# PR9002.net
KiCad netlist of a schematic drawn in EAGLE
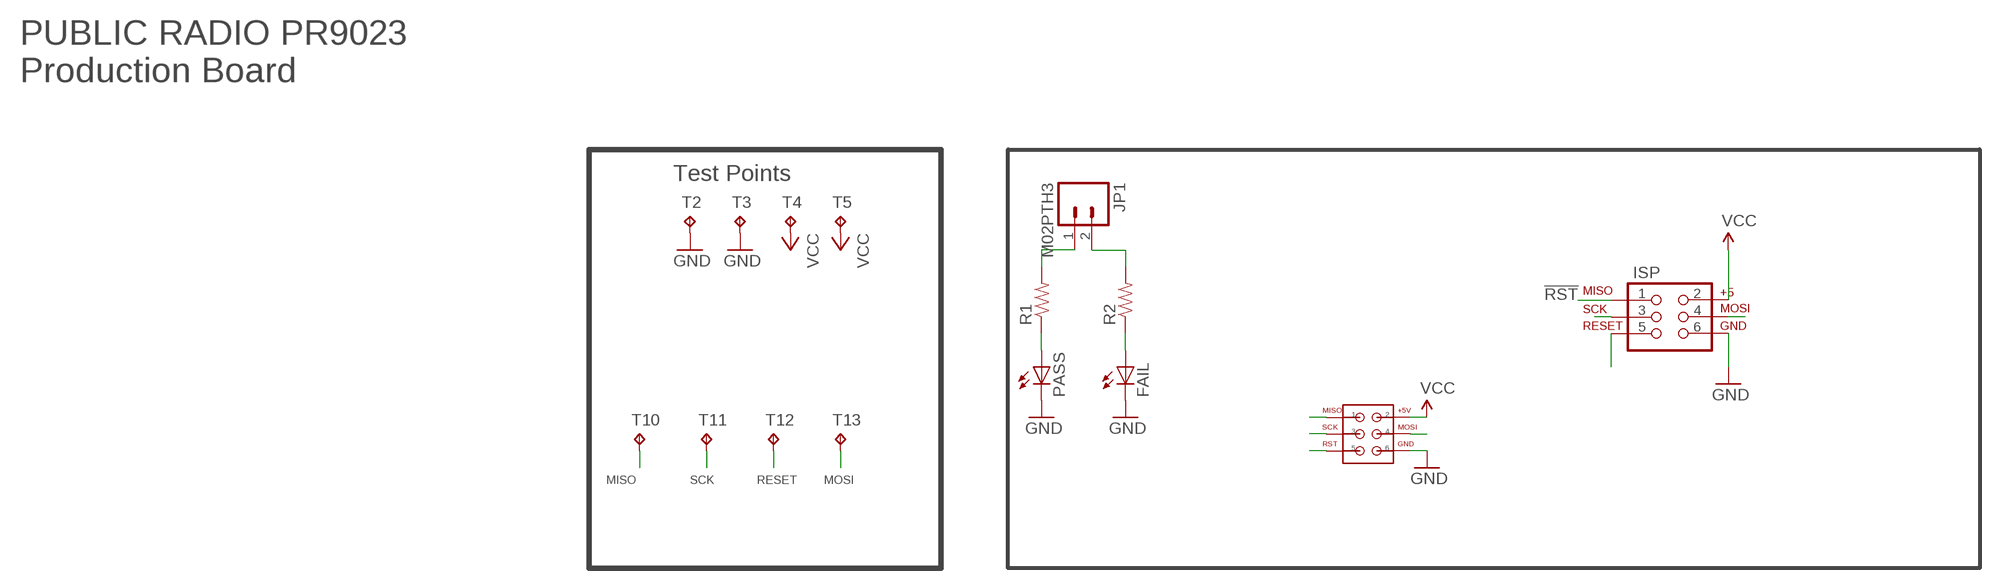
[diagram p0: schematic, sheet 1]

(export (version "E")
  (design (tool "Eeschema 10.0.6"))
  (components
    (comp (ref "FAIL")
      (value "LED5MM")
      (footprint "eagle-import:LED5MM")
      (libsource (lib "eagle-import") (part "LED5MM"))
    )
    (comp (ref "ISP")
      (value "AVR_SPI_PRG_6NS")
      (footprint "eagle-import:2X3-NS")
      (libsource (lib "eagle-import") (part "AVR_SPI_PRG_6NS"))
    )
    (comp (ref "JP1")
      (value "M02PTH3")
      (footprint "eagle-import:1X02_LONGPADS")
      (libsource (lib "eagle-import") (part "M02PTH3"))
    )
    (comp (ref "PASS")
      (value "LED5MM")
      (footprint "eagle-import:LED5MM")
      (libsource (lib "eagle-import") (part "LED5MM"))
    )
    (comp (ref "R1")
      (value "RESISTORPTH-1/4W-VERT")
      (footprint "eagle-import:AXIAL-0.1")
      (libsource (lib "eagle-import") (part "RESISTORPTH-1/4W-VERT"))
    )
    (comp (ref "R2")
      (value "RESISTORPTH-1/4W-VERT")
      (footprint "eagle-import:AXIAL-0.1")
      (libsource (lib "eagle-import") (part "RESISTORPTH-1/4W-VERT"))
    )
    (comp (ref "T2")
      (value "PR9001_TESTPOINT")
      (footprint "eagle-import:PR9001_TESTPOINT")
      (libsource (lib "eagle-import") (part "PR9001_TESTPOINT"))
    )
    (comp (ref "T3")
      (value "PR9001_TESTPOINT")
      (footprint "eagle-import:PR9001_TESTPOINT")
      (libsource (lib "eagle-import") (part "PR9001_TESTPOINT"))
    )
    (comp (ref "T4")
      (value "PR9001_TESTPOINT")
      (footprint "eagle-import:PR9001_TESTPOINT")
      (libsource (lib "eagle-import") (part "PR9001_TESTPOINT"))
    )
    (comp (ref "T5")
      (value "PR9001_TESTPOINT")
      (footprint "eagle-import:PR9001_TESTPOINT")
      (libsource (lib "eagle-import") (part "PR9001_TESTPOINT"))
    )
    (comp (ref "T10")
      (value "PR9001_TESTPOINT")
      (footprint "eagle-import:PR9001_TESTPOINT")
      (libsource (lib "eagle-import") (part "PR9001_TESTPOINT"))
    )
    (comp (ref "T11")
      (value "PR9001_TESTPOINT")
      (footprint "eagle-import:PR9001_TESTPOINT")
      (libsource (lib "eagle-import") (part "PR9001_TESTPOINT"))
    )
    (comp (ref "T12")
      (value "PR9001_TESTPOINT")
      (footprint "eagle-import:PR9001_TESTPOINT")
      (libsource (lib "eagle-import") (part "PR9001_TESTPOINT"))
    )
    (comp (ref "T13")
      (value "PR9001_TESTPOINT")
      (footprint "eagle-import:PR9001_TESTPOINT")
      (libsource (lib "eagle-import") (part "PR9001_TESTPOINT"))
    )
    (comp (ref "U$1")
      (value "ISP_POGOBED_S19_501")
      (footprint "eagle-import:ISP_POGOBED_S19_501")
      (libsource (lib "eagle-import") (part "ISP_POGOBED_S19_501"))
    )
  )
  (nets
    (net (code "1") (name "/RESET") (class "Default")
      (node (ref "ISP") (pin "5") (pinfunction "5_5") (pintype "passive"))
      (node (ref "T12") (pin "P$1") (pinfunction "TP_P$1") (pintype "input"))
      (node (ref "U$1") (pin "P$5") (pinfunction "P$5_P$5") (pintype "bidirectional"))
    )
    (net (code "2") (name "/SCLK") (class "Default")
      (node (ref "ISP") (pin "3") (pinfunction "3_3") (pintype "passive"))
      (node (ref "T11") (pin "P$1") (pinfunction "TP_P$1") (pintype "input"))
      (node (ref "U$1") (pin "P$3") (pinfunction "P$3_P$3") (pintype "bidirectional"))
    )
    (net (code "3") (name "/SDIO") (class "Default")
      (node (ref "ISP") (pin "4") (pinfunction "4_4") (pintype "passive"))
      (node (ref "T13") (pin "P$1") (pinfunction "TP_P$1") (pintype "input"))
      (node (ref "U$1") (pin "P$4") (pinfunction "P$4_P$4") (pintype "bidirectional"))
    )
    (net (code "4") (name "/~{RST}") (class "Default")
      (node (ref "ISP") (pin "1") (pinfunction "1_1") (pintype "passive"))
      (node (ref "T10") (pin "P$1") (pinfunction "TP_P$1") (pintype "input"))
      (node (ref "U$1") (pin "P$1") (pinfunction "P$1_P$1") (pintype "bidirectional"))
    )
    (net (code "5") (name "GND") (class "Default")
      (node (ref "FAIL") (pin "K") (pinfunction "C_K") (pintype "passive"))
      (node (ref "ISP") (pin "6") (pinfunction "6_6") (pintype "passive"))
      (node (ref "PASS") (pin "K") (pinfunction "C_K") (pintype "passive"))
      (node (ref "T2") (pin "P$1") (pinfunction "TP_P$1") (pintype "input"))
      (node (ref "T3") (pin "P$1") (pinfunction "TP_P$1") (pintype "input"))
      (node (ref "U$1") (pin "P$6") (pinfunction "P$6_P$6") (pintype "bidirectional"))
    )
    (net (code "6") (name "Net-(R1-1)") (class "Default")
      (node (ref "PASS") (pin "A") (pinfunction "A_A") (pintype "passive"))
      (node (ref "R1") (pin "P$1") (pinfunction "1_P$1") (pintype "passive"))
    )
    (net (code "7") (name "Net-(R1-2)") (class "Default")
      (node (ref "JP1") (pin "1") (pinfunction "1_1") (pintype "passive"))
      (node (ref "R1") (pin "P$2") (pinfunction "2_P$2") (pintype "passive"))
    )
    (net (code "8") (name "Net-(R2-1)") (class "Default")
      (node (ref "FAIL") (pin "A") (pinfunction "A_A") (pintype "passive"))
      (node (ref "R2") (pin "P$1") (pinfunction "1_P$1") (pintype "passive"))
    )
    (net (code "9") (name "Net-(R2-2)") (class "Default")
      (node (ref "JP1") (pin "2") (pinfunction "2_2") (pintype "passive"))
      (node (ref "R2") (pin "P$2") (pinfunction "2_P$2") (pintype "passive"))
    )
    (net (code "10") (name "VCC") (class "Default")
      (node (ref "ISP") (pin "2") (pinfunction "2_2") (pintype "passive"))
      (node (ref "T4") (pin "P$1") (pinfunction "TP_P$1") (pintype "input"))
      (node (ref "T5") (pin "P$1") (pinfunction "TP_P$1") (pintype "input"))
      (node (ref "U$1") (pin "P$2") (pinfunction "P$2_P$2") (pintype "bidirectional"))
    )
  )
)
